# XRP_Controller_Beta.net
KiCad netlist of a schematic drawn in EAGLE
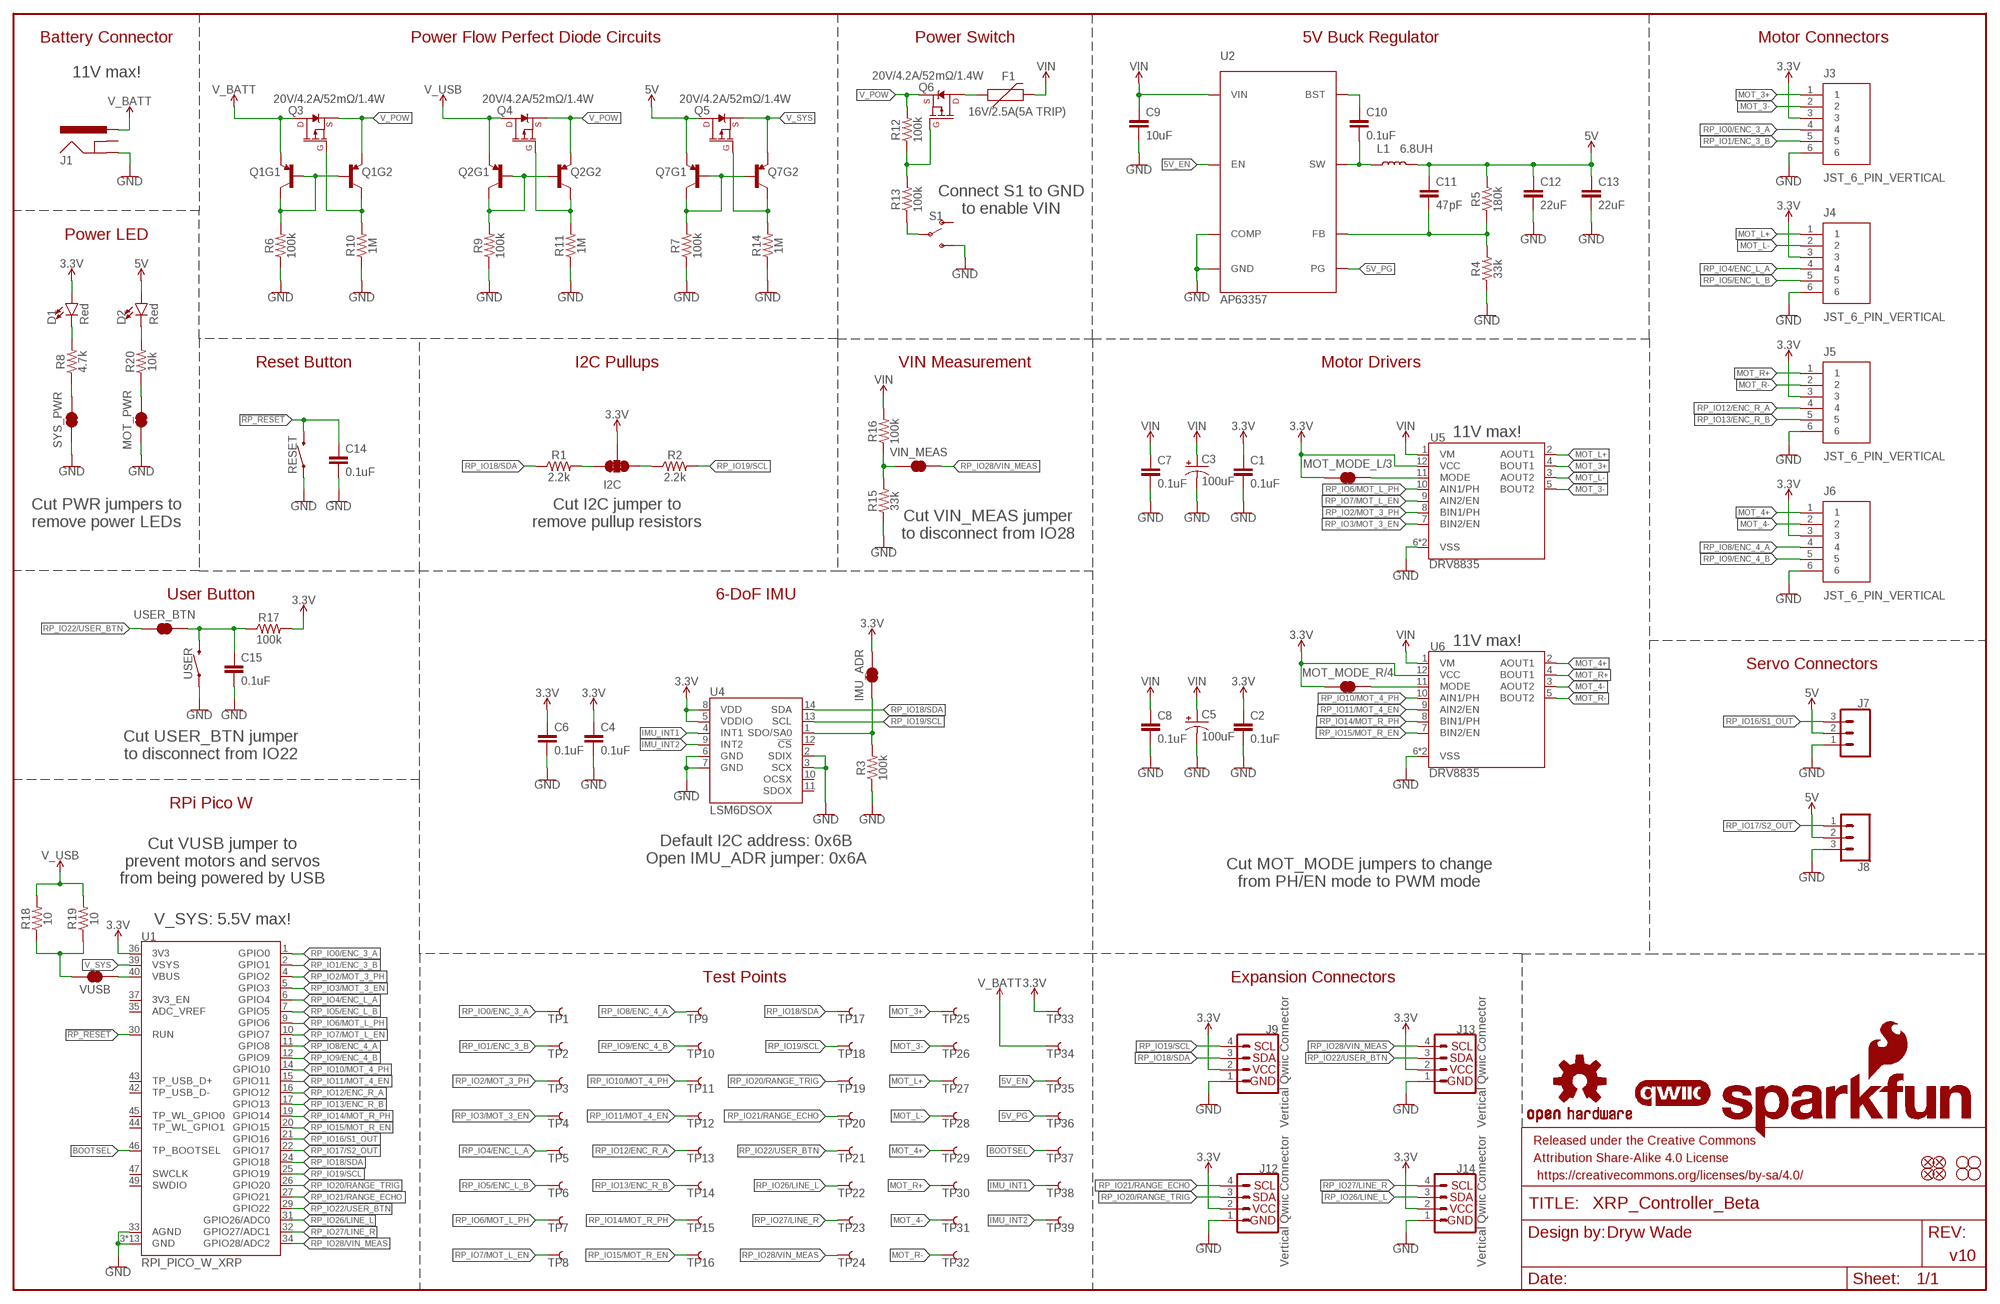
[diagram p0: schematic, sheet 1]

(export (version "E")
  (design (tool "Eeschema 10.0.6"))
  (components
    (comp (ref "C1")
      (value "0.1uF")
      (footprint "eagle-import:0603")
      (libsource (lib "eagle-import") (part "0.1UF-0603-25V-(+80/-20%)"))
    )
    (comp (ref "C2")
      (value "0.1uF")
      (footprint "eagle-import:0603")
      (libsource (lib "eagle-import") (part "0.1UF-0603-25V-(+80/-20%)"))
    )
    (comp (ref "C3")
      (value "100uF")
      (footprint "eagle-import:PANASONIC_D")
      (libsource (lib "eagle-import") (part "100UF-POLAR-25V-20%-SMD(ELEC)"))
    )
    (comp (ref "C4")
      (value "0.1uF")
      (footprint "eagle-import:0603")
      (libsource (lib "eagle-import") (part "0.1UF-0603-25V-(+80/-20%)"))
    )
    (comp (ref "C5")
      (value "100uF")
      (footprint "eagle-import:PANASONIC_D")
      (libsource (lib "eagle-import") (part "100UF-POLAR-25V-20%-SMD(ELEC)"))
    )
    (comp (ref "C6")
      (value "0.1uF")
      (footprint "eagle-import:0603")
      (libsource (lib "eagle-import") (part "0.1UF-0603-25V-(+80/-20%)"))
    )
    (comp (ref "C7")
      (value "0.1uF")
      (footprint "eagle-import:0603")
      (libsource (lib "eagle-import") (part "0.1UF-0603-25V-(+80/-20%)"))
    )
    (comp (ref "C8")
      (value "0.1uF")
      (footprint "eagle-import:0603")
      (libsource (lib "eagle-import") (part "0.1UF-0603-25V-(+80/-20%)"))
    )
    (comp (ref "C9")
      (value "10uF")
      (footprint "eagle-import:0805")
      (libsource (lib "eagle-import") (part "10UF-0805-25V-10%"))
    )
    (comp (ref "C10")
      (value "0.1uF")
      (footprint "eagle-import:0603")
      (libsource (lib "eagle-import") (part "0.1UF-0603-25V-(+80/-20%)"))
    )
    (comp (ref "C11")
      (value "47pF")
      (footprint "eagle-import:0603")
      (libsource (lib "eagle-import") (part "47PF-0603-50V-5%"))
    )
    (comp (ref "C12")
      (value "22uF")
      (footprint "eagle-import:0805")
      (libsource (lib "eagle-import") (part "22UF-0805-16V-20%"))
    )
    (comp (ref "C13")
      (value "22uF")
      (footprint "eagle-import:0805")
      (libsource (lib "eagle-import") (part "22UF-0805-16V-20%"))
    )
    (comp (ref "C14")
      (value "0.1uF")
      (footprint "eagle-import:0603")
      (libsource (lib "eagle-import") (part "0.1UF-0603-25V-(+80/-20%)"))
    )
    (comp (ref "C15")
      (value "0.1uF")
      (footprint "eagle-import:0603")
      (libsource (lib "eagle-import") (part "0.1UF-0603-25V-(+80/-20%)"))
    )
    (comp (ref "D1")
      (value "Red")
      (footprint "eagle-import:LED-0603")
      (libsource (lib "eagle-import") (part "LED-RED_0603-KB"))
    )
    (comp (ref "D2")
      (value "Red")
      (footprint "eagle-import:LED-0603")
      (libsource (lib "eagle-import") (part "LED-RED_0603-KB"))
    )
    (comp (ref "F1")
      (value "16V/2.5A(5A TRIP)")
      (footprint "eagle-import:1812")
      (libsource (lib "eagle-import") (part "PPTC_16V_2.5A"))
    )
    (comp (ref "FD1")
      (value "FIDUCIAL1X2")
      (footprint "eagle-import:FIDUCIAL-1X2")
      (libsource (lib "eagle-import") (part "FIDUCIAL1X2"))
    )
    (comp (ref "FD2")
      (value "FIDUCIAL1X2")
      (footprint "eagle-import:FIDUCIAL-1X2")
      (libsource (lib "eagle-import") (part "FIDUCIAL1X2"))
    )
    (comp (ref "FD3")
      (value "FIDUCIAL1X2")
      (footprint "eagle-import:FIDUCIAL-1X2")
      (libsource (lib "eagle-import") (part "FIDUCIAL1X2"))
    )
    (comp (ref "FD4")
      (value "FIDUCIAL1X2")
      (footprint "eagle-import:FIDUCIAL-1X2")
      (libsource (lib "eagle-import") (part "FIDUCIAL1X2"))
    )
    (comp (ref "FRAME1")
      (value "FRAME-LEDGER")
      (footprint "eagle-import:CREATIVE_COMMONS")
      (libsource (lib "eagle-import") (part "FRAME-LEDGER"))
    )
    (comp (ref "H1")
      (value "STAND-OFF")
      (footprint "eagle-import:STAND-OFF")
      (libsource (lib "eagle-import") (part "STAND-OFF"))
    )
    (comp (ref "H2")
      (value "STAND-OFF")
      (footprint "eagle-import:STAND-OFF")
      (libsource (lib "eagle-import") (part "STAND-OFF"))
    )
    (comp (ref "H3")
      (value "STAND-OFF")
      (footprint "eagle-import:STAND-OFF")
      (libsource (lib "eagle-import") (part "STAND-OFF"))
    )
    (comp (ref "H4")
      (value "STAND-OFF")
      (footprint "eagle-import:STAND-OFF")
      (libsource (lib "eagle-import") (part "STAND-OFF"))
    )
    (comp (ref "I2C")
      (value "JUMPER-SMT_3_2-NC_TRACE_SILK")
      (footprint "eagle-import:SMT-JUMPER_3_2-NC_TRACE_SILK")
      (libsource (lib "eagle-import") (part "JUMPER-SMT_3_2-NC_TRACE_SILK"))
    )
    (comp (ref "IMU_ADR")
      (value "JUMPER-SMT_2_NC_TRACE_SILK")
      (footprint "eagle-import:SMT-JUMPER_2_NC_TRACE_SILK")
      (libsource (lib "eagle-import") (part "JUMPER-SMT_2_NC_TRACE_SILK"))
    )
    (comp (ref "J1")
      (value "POWER_JACKPOWER_JACK_SLOT")
      (footprint "eagle-import:POWER_JACK_PTH_SLOT")
      (libsource (lib "eagle-import") (part "POWER_JACKPOWER_JACK_SLOT"))
    )
    (comp (ref "J3")
      (value "JST_6_PIN_VERTICAL")
      (footprint "eagle-import:JST-6-SMD-VERT-1.0MM")
      (libsource (lib "eagle-import") (part "JST_6_PIN_VERTICAL"))
    )
    (comp (ref "J4")
      (value "JST_6_PIN_VERTICAL")
      (footprint "eagle-import:JST-6-SMD-VERT-1.0MM")
      (libsource (lib "eagle-import") (part "JST_6_PIN_VERTICAL"))
    )
    (comp (ref "J5")
      (value "JST_6_PIN_VERTICAL")
      (footprint "eagle-import:JST-6-SMD-VERT-1.0MM")
      (libsource (lib "eagle-import") (part "JST_6_PIN_VERTICAL"))
    )
    (comp (ref "J6")
      (value "JST_6_PIN_VERTICAL")
      (footprint "eagle-import:JST-6-SMD-VERT-1.0MM")
      (libsource (lib "eagle-import") (part "JST_6_PIN_VERTICAL"))
    )
    (comp (ref "J7")
      (value "CONN_03LOCK_NO_SILK")
      (footprint "eagle-import:1X03_LOCK_NO_SILK")
      (libsource (lib "eagle-import") (part "CONN_03LOCK_NO_SILK"))
    )
    (comp (ref "J8")
      (value "CONN_03LOCK_NO_SILK")
      (footprint "eagle-import:1X03_LOCK_NO_SILK")
      (libsource (lib "eagle-import") (part "CONN_03LOCK_NO_SILK"))
    )
    (comp (ref "J9")
      (value "Vertical Qwiic Connector")
      (footprint "eagle-import:JST04_1MM_VERT")
      (libsource (lib "eagle-import") (part "QWIIC_CONNECTOR"))
    )
    (comp (ref "J12")
      (value "Vertical Qwiic Connector")
      (footprint "eagle-import:JST04_1MM_VERT")
      (libsource (lib "eagle-import") (part "QWIIC_CONNECTOR"))
    )
    (comp (ref "J13")
      (value "Vertical Qwiic Connector")
      (footprint "eagle-import:JST04_1MM_VERT")
      (libsource (lib "eagle-import") (part "QWIIC_CONNECTOR"))
    )
    (comp (ref "J14")
      (value "Vertical Qwiic Connector")
      (footprint "eagle-import:JST04_1MM_VERT")
      (libsource (lib "eagle-import") (part "QWIIC_CONNECTOR"))
    )
    (comp (ref "L1")
      (value "6.8UH")
      (footprint "eagle-import:07A7_6U8H")
      (libsource (lib "eagle-import") (part "6.8UH"))
    )
    (comp (ref "LOGO1")
      (value "OSHW-LOGOS")
      (footprint "eagle-import:OSHW-LOGO-S")
      (libsource (lib "eagle-import") (part "OSHW-LOGOS"))
    )
    (comp (ref "LOGO3")
      (value "SFE_LOGO_NAME_FLAME.3_INCH")
      (footprint "eagle-import:SFE_LOGO_NAME_FLAME_.3")
      (libsource (lib "eagle-import") (part "SFE_LOGO_NAME_FLAME.3_INCH"))
    )
    (comp (ref "MOT_MODE_L/3")
      (value "JUMPER-SMT_2_NC_TRACE_SILK")
      (footprint "eagle-import:SMT-JUMPER_2_NC_TRACE_SILK")
      (libsource (lib "eagle-import") (part "JUMPER-SMT_2_NC_TRACE_SILK"))
    )
    (comp (ref "MOT_MODE_R/4")
      (value "JUMPER-SMT_2_NC_TRACE_SILK")
      (footprint "eagle-import:SMT-JUMPER_2_NC_TRACE_SILK")
      (libsource (lib "eagle-import") (part "JUMPER-SMT_2_NC_TRACE_SILK"))
    )
    (comp (ref "MOT_PWR")
      (value "JUMPER-SMT_2_NC_TRACE_SILK")
      (footprint "eagle-import:SMT-JUMPER_2_NC_TRACE_SILK")
      (libsource (lib "eagle-import") (part "JUMPER-SMT_2_NC_TRACE_SILK"))
    )
    (comp (ref "Q1")
      (value "TRANS_PNP_DUALSOT-363")
      (footprint "eagle-import:SOT363_PHILIPS")
      (libsource (lib "eagle-import") (part "TRANS_PNP_DUALSOT-363"))
    )
    (comp (ref "Q2")
      (value "TRANS_PNP_DUALSOT-363")
      (footprint "eagle-import:SOT363_PHILIPS")
      (libsource (lib "eagle-import") (part "TRANS_PNP_DUALSOT-363"))
    )
    (comp (ref "Q3")
      (value "20V/4.2A/52mΩ/1.4W")
      (footprint "eagle-import:SOT23-3")
      (libsource (lib "eagle-import") (part "MOSFET_PCH-DMG2305UX-7"))
    )
    (comp (ref "Q4")
      (value "20V/4.2A/52mΩ/1.4W")
      (footprint "eagle-import:SOT23-3")
      (libsource (lib "eagle-import") (part "MOSFET_PCH-DMG2305UX-7"))
    )
    (comp (ref "Q5")
      (value "20V/4.2A/52mΩ/1.4W")
      (footprint "eagle-import:SOT23-3")
      (libsource (lib "eagle-import") (part "MOSFET_PCH-DMG2305UX-7"))
    )
    (comp (ref "Q6")
      (value "20V/4.2A/52mΩ/1.4W")
      (footprint "eagle-import:SOT23-3")
      (libsource (lib "eagle-import") (part "MOSFET_PCH-DMG2305UX-7"))
    )
    (comp (ref "Q7")
      (value "TRANS_PNP_DUALSOT-363")
      (footprint "eagle-import:SOT363_PHILIPS")
      (libsource (lib "eagle-import") (part "TRANS_PNP_DUALSOT-363"))
    )
    (comp (ref "R1")
      (value "2.2k")
      (footprint "eagle-import:0603")
      (libsource (lib "eagle-import") (part "2.2KOHM-0603-1/10W-1%"))
    )
    (comp (ref "R2")
      (value "2.2k")
      (footprint "eagle-import:0603")
      (libsource (lib "eagle-import") (part "2.2KOHM-0603-1/10W-1%"))
    )
    (comp (ref "R3")
      (value "100k")
      (footprint "eagle-import:0603")
      (libsource (lib "eagle-import") (part "100KOHM-0603-1/10W-1%"))
    )
    (comp (ref "R4")
      (value "33k")
      (footprint "eagle-import:0603")
      (libsource (lib "eagle-import") (part "33KOHM-0603-1/10W-1%"))
    )
    (comp (ref "R5")
      (value "180k")
      (footprint "eagle-import:0603")
      (libsource (lib "eagle-import") (part "180KOHM-0603-1/10W-1%"))
    )
    (comp (ref "R6")
      (value "100k")
      (footprint "eagle-import:0603")
      (libsource (lib "eagle-import") (part "100KOHM-0603-1/10W-1%"))
    )
    (comp (ref "R7")
      (value "100k")
      (footprint "eagle-import:0603")
      (libsource (lib "eagle-import") (part "100KOHM-0603-1/10W-1%"))
    )
    (comp (ref "R8")
      (value "4.7k")
      (footprint "eagle-import:0603")
      (libsource (lib "eagle-import") (part "4.7KOHM-0603-1/10W-1%"))
    )
    (comp (ref "R9")
      (value "100k")
      (footprint "eagle-import:0603")
      (libsource (lib "eagle-import") (part "100KOHM-0603-1/10W-1%"))
    )
    (comp (ref "R10")
      (value "1M")
      (footprint "eagle-import:0603")
      (libsource (lib "eagle-import") (part "1MOHM-0603-1/4W-5%"))
    )
    (comp (ref "R11")
      (value "1M")
      (footprint "eagle-import:0603")
      (libsource (lib "eagle-import") (part "1MOHM-0603-1/4W-5%"))
    )
    (comp (ref "R12")
      (value "100k")
      (footprint "eagle-import:0603")
      (libsource (lib "eagle-import") (part "100KOHM-0603-1/10W-1%"))
    )
    (comp (ref "R13")
      (value "100k")
      (footprint "eagle-import:0603")
      (libsource (lib "eagle-import") (part "100KOHM-0603-1/10W-1%"))
    )
    (comp (ref "R14")
      (value "1M")
      (footprint "eagle-import:0603")
      (libsource (lib "eagle-import") (part "1MOHM-0603-1/4W-5%"))
    )
    (comp (ref "R15")
      (value "33k")
      (footprint "eagle-import:0603")
      (libsource (lib "eagle-import") (part "33KOHM-0603-1/10W-1%"))
    )
    (comp (ref "R16")
      (value "100k")
      (footprint "eagle-import:0603")
      (libsource (lib "eagle-import") (part "100KOHM-0603-1/10W-1%"))
    )
    (comp (ref "R17")
      (value "100k")
      (footprint "eagle-import:0603")
      (libsource (lib "eagle-import") (part "100KOHM-0603-1/10W-1%"))
    )
    (comp (ref "R18")
      (value "10")
      (footprint "eagle-import:1206")
      (libsource (lib "eagle-import") (part "10OHM-1206-1/4W-1%"))
    )
    (comp (ref "R19")
      (value "10")
      (footprint "eagle-import:1206")
      (libsource (lib "eagle-import") (part "10OHM-1206-1/4W-1%"))
    )
    (comp (ref "R20")
      (value "10k")
      (footprint "eagle-import:0603")
      (libsource (lib "eagle-import") (part "10KOHM-0603-1/10W-1%"))
    )
    (comp (ref "RESET")
      (value "MOMENTARY-SWITCH-SPST-SMD-4.6X2.8MM")
      (footprint "eagle-import:TACTILE_SWITCH_SMD_4.6X2.8MM")
      (libsource (lib "eagle-import") (part "MOMENTARY-SWITCH-SPST-SMD-4.6X2.8MM"))
    )
    (comp (ref "S1")
      (value "SWITCH-SPDT-SMD-RIGHT-ANGLE")
      (footprint "eagle-import:SWITCH_SPST_SMD_A")
      (libsource (lib "eagle-import") (part "SWITCH-SPDT-SMD-RIGHT-ANGLE"))
    )
    (comp (ref "SYS_PWR")
      (value "JUMPER-SMT_2_NC_TRACE_SILK")
      (footprint "eagle-import:SMT-JUMPER_2_NC_TRACE_SILK")
      (libsource (lib "eagle-import") (part "JUMPER-SMT_2_NC_TRACE_SILK"))
    )
    (comp (ref "TP1")
      (value "TEST-POINT3X5")
      (footprint "eagle-import:PAD.03X.05")
      (libsource (lib "eagle-import") (part "TEST-POINT3X5"))
    )
    (comp (ref "TP2")
      (value "TEST-POINT3X5")
      (footprint "eagle-import:PAD.03X.05")
      (libsource (lib "eagle-import") (part "TEST-POINT3X5"))
    )
    (comp (ref "TP3")
      (value "TEST-POINT3X5")
      (footprint "eagle-import:PAD.03X.05")
      (libsource (lib "eagle-import") (part "TEST-POINT3X5"))
    )
    (comp (ref "TP4")
      (value "TEST-POINT3X5")
      (footprint "eagle-import:PAD.03X.05")
      (libsource (lib "eagle-import") (part "TEST-POINT3X5"))
    )
    (comp (ref "TP5")
      (value "TEST-POINT3X5")
      (footprint "eagle-import:PAD.03X.05")
      (libsource (lib "eagle-import") (part "TEST-POINT3X5"))
    )
    (comp (ref "TP6")
      (value "TEST-POINT3X5")
      (footprint "eagle-import:PAD.03X.05")
      (libsource (lib "eagle-import") (part "TEST-POINT3X5"))
    )
    (comp (ref "TP7")
      (value "TEST-POINT3X5")
      (footprint "eagle-import:PAD.03X.05")
      (libsource (lib "eagle-import") (part "TEST-POINT3X5"))
    )
    (comp (ref "TP8")
      (value "TEST-POINT3X5")
      (footprint "eagle-import:PAD.03X.05")
      (libsource (lib "eagle-import") (part "TEST-POINT3X5"))
    )
    (comp (ref "TP9")
      (value "TEST-POINT3X5")
      (footprint "eagle-import:PAD.03X.05")
      (libsource (lib "eagle-import") (part "TEST-POINT3X5"))
    )
    (comp (ref "TP10")
      (value "TEST-POINT3X5")
      (footprint "eagle-import:PAD.03X.05")
      (libsource (lib "eagle-import") (part "TEST-POINT3X5"))
    )
    (comp (ref "TP11")
      (value "TEST-POINT3X5")
      (footprint "eagle-import:PAD.03X.05")
      (libsource (lib "eagle-import") (part "TEST-POINT3X5"))
    )
    (comp (ref "TP12")
      (value "TEST-POINT3X5")
      (footprint "eagle-import:PAD.03X.05")
      (libsource (lib "eagle-import") (part "TEST-POINT3X5"))
    )
    (comp (ref "TP13")
      (value "TEST-POINT3X5")
      (footprint "eagle-import:PAD.03X.05")
      (libsource (lib "eagle-import") (part "TEST-POINT3X5"))
    )
    (comp (ref "TP14")
      (value "TEST-POINT3X5")
      (footprint "eagle-import:PAD.03X.05")
      (libsource (lib "eagle-import") (part "TEST-POINT3X5"))
    )
    (comp (ref "TP15")
      (value "TEST-POINT3X5")
      (footprint "eagle-import:PAD.03X.05")
      (libsource (lib "eagle-import") (part "TEST-POINT3X5"))
    )
    (comp (ref "TP16")
      (value "TEST-POINT3X5")
      (footprint "eagle-import:PAD.03X.05")
      (libsource (lib "eagle-import") (part "TEST-POINT3X5"))
    )
    (comp (ref "TP17")
      (value "TEST-POINT3X5")
      (footprint "eagle-import:PAD.03X.05")
      (libsource (lib "eagle-import") (part "TEST-POINT3X5"))
    )
    (comp (ref "TP18")
      (value "TEST-POINT3X5")
      (footprint "eagle-import:PAD.03X.05")
      (libsource (lib "eagle-import") (part "TEST-POINT3X5"))
    )
    (comp (ref "TP19")
      (value "TEST-POINT3X5")
      (footprint "eagle-import:PAD.03X.05")
      (libsource (lib "eagle-import") (part "TEST-POINT3X5"))
    )
    (comp (ref "TP20")
      (value "TEST-POINT3X5")
      (footprint "eagle-import:PAD.03X.05")
      (libsource (lib "eagle-import") (part "TEST-POINT3X5"))
    )
    (comp (ref "TP21")
      (value "TEST-POINT3X5")
      (footprint "eagle-import:PAD.03X.05")
      (libsource (lib "eagle-import") (part "TEST-POINT3X5"))
    )
    (comp (ref "TP22")
      (value "TEST-POINT3X5")
      (footprint "eagle-import:PAD.03X.05")
      (libsource (lib "eagle-import") (part "TEST-POINT3X5"))
    )
    (comp (ref "TP23")
      (value "TEST-POINT3X5")
      (footprint "eagle-import:PAD.03X.05")
      (libsource (lib "eagle-import") (part "TEST-POINT3X5"))
    )
    (comp (ref "TP24")
      (value "TEST-POINT3X5")
      (footprint "eagle-import:PAD.03X.05")
      (libsource (lib "eagle-import") (part "TEST-POINT3X5"))
    )
    (comp (ref "TP25")
      (value "TEST-POINT3X5")
      (footprint "eagle-import:PAD.03X.05")
      (libsource (lib "eagle-import") (part "TEST-POINT3X5"))
    )
    (comp (ref "TP26")
      (value "TEST-POINT3X5")
      (footprint "eagle-import:PAD.03X.05")
      (libsource (lib "eagle-import") (part "TEST-POINT3X5"))
    )
    (comp (ref "TP27")
      (value "TEST-POINT3X5")
      (footprint "eagle-import:PAD.03X.05")
      (libsource (lib "eagle-import") (part "TEST-POINT3X5"))
    )
    (comp (ref "TP28")
      (value "TEST-POINT3X5")
      (footprint "eagle-import:PAD.03X.05")
      (libsource (lib "eagle-import") (part "TEST-POINT3X5"))
    )
    (comp (ref "TP29")
      (value "TEST-POINT3X5")
      (footprint "eagle-import:PAD.03X.05")
      (libsource (lib "eagle-import") (part "TEST-POINT3X5"))
    )
    (comp (ref "TP30")
      (value "TEST-POINT3X5")
      (footprint "eagle-import:PAD.03X.05")
      (libsource (lib "eagle-import") (part "TEST-POINT3X5"))
    )
    (comp (ref "TP31")
      (value "TEST-POINT3X5")
      (footprint "eagle-import:PAD.03X.05")
      (libsource (lib "eagle-import") (part "TEST-POINT3X5"))
    )
    (comp (ref "TP32")
      (value "TEST-POINT3X5")
      (footprint "eagle-import:PAD.03X.05")
      (libsource (lib "eagle-import") (part "TEST-POINT3X5"))
    )
    (comp (ref "TP33")
      (value "TEST-POINT3X5")
      (footprint "eagle-import:PAD.03X.05")
      (libsource (lib "eagle-import") (part "TEST-POINT3X5"))
    )
    (comp (ref "TP34")
      (value "TEST-POINT3X5")
      (footprint "eagle-import:PAD.03X.05")
      (libsource (lib "eagle-import") (part "TEST-POINT3X5"))
    )
    (comp (ref "TP35")
      (value "TEST-POINT3X5")
      (footprint "eagle-import:PAD.03X.05")
      (libsource (lib "eagle-import") (part "TEST-POINT3X5"))
    )
    (comp (ref "TP36")
      (value "TEST-POINT3X5")
      (footprint "eagle-import:PAD.03X.05")
      (libsource (lib "eagle-import") (part "TEST-POINT3X5"))
    )
    (comp (ref "TP37")
      (value "TEST-POINT3X5")
      (footprint "eagle-import:PAD.03X.05")
      (libsource (lib "eagle-import") (part "TEST-POINT3X5"))
    )
    (comp (ref "TP38")
      (value "TEST-POINT3X5")
      (footprint "eagle-import:PAD.03X.05")
      (libsource (lib "eagle-import") (part "TEST-POINT3X5"))
    )
    (comp (ref "TP39")
      (value "TEST-POINT3X5")
      (footprint "eagle-import:PAD.03X.05")
      (libsource (lib "eagle-import") (part "TEST-POINT3X5"))
    )
    (comp (ref "U$98")
      (value "QWIIC_LOGO_5MM_INVERTED")
      (footprint "eagle-import:QWIIC_5MM_INVERTED")
      (libsource (lib "eagle-import") (part "QWIIC_LOGO_5MM_INVERTED"))
    )
    (comp (ref "U1")
      (value "RPI_PICO_W_XRP")
      (footprint "eagle-import:RPI_PICO_W")
      (libsource (lib "eagle-import") (part "RPI_PICO_W_XRP"))
    )
    (comp (ref "U2")
      (value "AP63357")
      (footprint "eagle-import:V-DFN3020-13")
      (libsource (lib "eagle-import") (part "AP63357"))
    )
    (comp (ref "U4")
      (value "LSM6DSOX")
      (footprint "eagle-import:LGA14L")
      (libsource (lib "eagle-import") (part "LSM6DSOX"))
    )
    (comp (ref "U5")
      (value "DRV8835")
      (footprint "eagle-import:WSON-12")
      (libsource (lib "eagle-import") (part "DRV883X"))
    )
    (comp (ref "U6")
      (value "DRV8835")
      (footprint "eagle-import:WSON-12")
      (libsource (lib "eagle-import") (part "DRV883X"))
    )
    (comp (ref "USER")
      (value "MOMENTARY-SWITCH-SPST-SMD-4.6X2.8MM")
      (footprint "eagle-import:TACTILE_SWITCH_SMD_4.6X2.8MM")
      (libsource (lib "eagle-import") (part "MOMENTARY-SWITCH-SPST-SMD-4.6X2.8MM"))
    )
    (comp (ref "USER_BTN")
      (value "JUMPER-SMT_2_NC_TRACE_SILK")
      (footprint "eagle-import:SMT-JUMPER_2_NC_TRACE_SILK")
      (libsource (lib "eagle-import") (part "JUMPER-SMT_2_NC_TRACE_SILK"))
    )
    (comp (ref "VIN_MEAS")
      (value "JUMPER-SMT_2_NC_TRACE_SILK")
      (footprint "eagle-import:SMT-JUMPER_2_NC_TRACE_SILK")
      (libsource (lib "eagle-import") (part "JUMPER-SMT_2_NC_TRACE_SILK"))
    )
    (comp (ref "VUSB")
      (value "JUMPER-SMT_2_NC_TRACE_SILK")
      (footprint "eagle-import:SMT-JUMPER_2_NC_TRACE_SILK")
      (libsource (lib "eagle-import") (part "JUMPER-SMT_2_NC_TRACE_SILK"))
    )
  )
  (nets
    (net (code "1") (name "/~{RP_RESET}") (class "Default")
      (node (ref "C14") (pin "1") (pinfunction "1_1") (pintype "passive"))
      (node (ref "RESET") (pin "3") (pinfunction "2_3") (pintype "passive"))
      (node (ref "RESET") (pin "4") (pinfunction "2_4") (pintype "passive"))
      (node (ref "U1") (pin "30") (pinfunction "RUN_30") (pintype "bidirectional"))
    )
    (net (code "2") (name "3.3V") (class "Default")
      (node (ref "C1") (pin "1") (pinfunction "1_1") (pintype "passive"))
      (node (ref "C2") (pin "1") (pinfunction "1_1") (pintype "passive"))
      (node (ref "C4") (pin "1") (pinfunction "1_1") (pintype "passive"))
      (node (ref "C6") (pin "1") (pinfunction "1_1") (pintype "passive"))
      (node (ref "D1") (pin "A") (pinfunction "A_A") (pintype "passive"))
      (node (ref "I2C") (pin "2") (pinfunction "2_2") (pintype "passive"))
      (node (ref "IMU_ADR") (pin "2") (pinfunction "2_2") (pintype "passive"))
      (node (ref "J12") (pin "2") (pinfunction "2_2") (pintype "power_in"))
      (node (ref "J13") (pin "2") (pinfunction "2_2") (pintype "power_in"))
      (node (ref "J14") (pin "2") (pinfunction "2_2") (pintype "power_in"))
      (node (ref "J3") (pin "3") (pinfunction "3_3") (pintype "bidirectional"))
      (node (ref "J4") (pin "3") (pinfunction "3_3") (pintype "bidirectional"))
      (node (ref "J5") (pin "3") (pinfunction "3_3") (pintype "bidirectional"))
      (node (ref "J6") (pin "3") (pinfunction "3_3") (pintype "bidirectional"))
      (node (ref "J9") (pin "2") (pinfunction "2_2") (pintype "power_in"))
      (node (ref "MOT_MODE_L/3") (pin "2") (pinfunction "2_2") (pintype "passive"))
      (node (ref "MOT_MODE_R/4") (pin "2") (pinfunction "2_2") (pintype "passive"))
      (node (ref "R17") (pin "2") (pinfunction "2_2") (pintype "passive"))
      (node (ref "TP33") (pin "1") (pinfunction "1_1") (pintype "bidirectional"))
      (node (ref "U1") (pin "36") (pinfunction "3V3_36") (pintype "bidirectional"))
      (node (ref "U4") (pin "5") (pinfunction "VDDIO_5") (pintype "bidirectional"))
      (node (ref "U4") (pin "8") (pinfunction "VDD_8") (pintype "bidirectional"))
      (node (ref "U5") (pin "12") (pinfunction "VCC_12") (pintype "bidirectional"))
      (node (ref "U6") (pin "12") (pinfunction "VCC_12") (pintype "bidirectional"))
    )
    (net (code "3") (name "5V") (class "Default")
      (node (ref "C11") (pin "1") (pinfunction "1_1") (pintype "passive"))
      (node (ref "C12") (pin "1") (pinfunction "1_1") (pintype "passive"))
      (node (ref "C13") (pin "1") (pinfunction "1_1") (pintype "passive"))
      (node (ref "D2") (pin "A") (pinfunction "A_A") (pintype "passive"))
      (node (ref "J7") (pin "2") (pinfunction "2_2") (pintype "passive"))
      (node (ref "J8") (pin "2") (pinfunction "2_2") (pintype "passive"))
      (node (ref "L1") (pin "P$2") (pinfunction "2_P$2") (pintype "passive"))
      (node (ref "Q5") (pin "3") (pinfunction "D_3") (pintype "bidirectional"))
      (node (ref "Q7") (pin "1") (pinfunction "E_1") (pintype "passive"))
      (node (ref "R5") (pin "2") (pinfunction "2_2") (pintype "passive"))
    )
    (net (code "4") (name "5V_EN") (class "Default")
      (node (ref "TP35") (pin "1") (pinfunction "1_1") (pintype "bidirectional"))
      (node (ref "U2") (pin "P$2") (pinfunction "EN_P$2") (pintype "bidirectional"))
    )
    (net (code "5") (name "5V_PG") (class "Default")
      (node (ref "TP36") (pin "1") (pinfunction "1_1") (pintype "bidirectional"))
      (node (ref "U2") (pin "P$5") (pinfunction "PG_P$5") (pintype "output"))
    )
    (net (code "6") (name "BOOTSEL") (class "Default")
      (node (ref "TP37") (pin "1") (pinfunction "1_1") (pintype "bidirectional"))
      (node (ref "U1") (pin "46") (pinfunction "TP_BOOTSEL_46") (pintype "bidirectional"))
    )
    (net (code "7") (name "GND") (class "Default")
      (node (ref "C1") (pin "2") (pinfunction "2_2") (pintype "passive"))
      (node (ref "C12") (pin "2") (pinfunction "2_2") (pintype "passive"))
      (node (ref "C13") (pin "2") (pinfunction "2_2") (pintype "passive"))
      (node (ref "C14") (pin "2") (pinfunction "2_2") (pintype "passive"))
      (node (ref "C15") (pin "2") (pinfunction "2_2") (pintype "passive"))
      (node (ref "C2") (pin "2") (pinfunction "2_2") (pintype "passive"))
      (node (ref "C3") (pin "-") (pinfunction "-_-") (pintype "passive"))
      (node (ref "C4") (pin "2") (pinfunction "2_2") (pintype "passive"))
      (node (ref "C5") (pin "-") (pinfunction "-_-") (pintype "passive"))
      (node (ref "C6") (pin "2") (pinfunction "2_2") (pintype "passive"))
      (node (ref "C7") (pin "2") (pinfunction "2_2") (pintype "passive"))
      (node (ref "C8") (pin "2") (pinfunction "2_2") (pintype "passive"))
      (node (ref "C9") (pin "2") (pinfunction "2_2") (pintype "passive"))
      (node (ref "J1") (pin "GND") (pinfunction "GND_GND") (pintype "bidirectional"))
      (node (ref "J12") (pin "1") (pinfunction "1_1") (pintype "power_in"))
      (node (ref "J13") (pin "1") (pinfunction "1_1") (pintype "power_in"))
      (node (ref "J14") (pin "1") (pinfunction "1_1") (pintype "power_in"))
      (node (ref "J3") (pin "6") (pinfunction "6_6") (pintype "bidirectional"))
      (node (ref "J4") (pin "6") (pinfunction "6_6") (pintype "bidirectional"))
      (node (ref "J5") (pin "6") (pinfunction "6_6") (pintype "bidirectional"))
      (node (ref "J6") (pin "6") (pinfunction "6_6") (pintype "bidirectional"))
      (node (ref "J7") (pin "1") (pinfunction "1_1") (pintype "passive"))
      (node (ref "J8") (pin "3") (pinfunction "3_3") (pintype "passive"))
      (node (ref "J9") (pin "1") (pinfunction "1_1") (pintype "power_in"))
      (node (ref "MOT_PWR") (pin "1") (pinfunction "1_1") (pintype "passive"))
      (node (ref "R10") (pin "1") (pinfunction "1_1") (pintype "passive"))
      (node (ref "R11") (pin "1") (pinfunction "1_1") (pintype "passive"))
      (node (ref "R14") (pin "1") (pinfunction "1_1") (pintype "passive"))
      (node (ref "R15") (pin "1") (pinfunction "1_1") (pintype "passive"))
      (node (ref "R3") (pin "1") (pinfunction "1_1") (pintype "passive"))
      (node (ref "R4") (pin "1") (pinfunction "1_1") (pintype "passive"))
      (node (ref "R6") (pin "1") (pinfunction "1_1") (pintype "passive"))
      (node (ref "R7") (pin "1") (pinfunction "1_1") (pintype "passive"))
      (node (ref "R9") (pin "1") (pinfunction "1_1") (pintype "passive"))
      (node (ref "RESET") (pin "1") (pinfunction "1_1") (pintype "passive"))
      (node (ref "RESET") (pin "2") (pinfunction "1_2") (pintype "passive"))
      (node (ref "S1") (pin "3") (pinfunction "S_3") (pintype "passive"))
      (node (ref "SYS_PWR") (pin "1") (pinfunction "1_1") (pintype "passive"))
      (node (ref "U1") (pin "13") (pinfunction "GND_13") (pintype "bidirectional"))
      (node (ref "U1") (pin "18") (pinfunction "GND_18") (pintype "bidirectional"))
      (node (ref "U1") (pin "23") (pinfunction "GND_23") (pintype "bidirectional"))
      (node (ref "U1") (pin "28") (pinfunction "GND_28") (pintype "bidirectional"))
      (node (ref "U1") (pin "3") (pinfunction "GND_3") (pintype "bidirectional"))
      (node (ref "U1") (pin "33") (pinfunction "AGND_33") (pintype "bidirectional"))
      (node (ref "U1") (pin "38") (pinfunction "GND_38") (pintype "bidirectional"))
      (node (ref "U1") (pin "41") (pinfunction "GND_41") (pintype "bidirectional"))
      (node (ref "U1") (pin "48") (pinfunction "GND_48") (pintype "bidirectional"))
      (node (ref "U1") (pin "8") (pinfunction "GND_8") (pintype "bidirectional"))
      (node (ref "U1") (pin "A") (pinfunction "GND_A") (pintype "bidirectional"))
      (node (ref "U1") (pin "B") (pinfunction "GND_B") (pintype "bidirectional"))
      (node (ref "U1") (pin "C") (pinfunction "GND_C") (pintype "bidirectional"))
      (node (ref "U1") (pin "D") (pinfunction "GND_D") (pintype "bidirectional"))
      (node (ref "U2") (pin "P$4") (pinfunction "COMP_P$4") (pintype "bidirectional"))
      (node (ref "U2") (pin "P$8") (pinfunction "GND_P$8") (pintype "power_in"))
      (node (ref "U4") (pin "2") (pinfunction "SDIX_2") (pintype "bidirectional"))
      (node (ref "U4") (pin "3") (pinfunction "SCX_3") (pintype "bidirectional"))
      (node (ref "U4") (pin "6") (pinfunction "GND_6") (pintype "bidirectional"))
      (node (ref "U4") (pin "7") (pinfunction "GND_7") (pintype "bidirectional"))
      (node (ref "U5") (pin "6") (pinfunction "VSS_6") (pintype "bidirectional"))
      (node (ref "U5") (pin "PAD") (pinfunction "VSS_PAD") (pintype "bidirectional"))
      (node (ref "U6") (pin "6") (pinfunction "VSS_6") (pintype "bidirectional"))
      (node (ref "U6") (pin "PAD") (pinfunction "VSS_PAD") (pintype "bidirectional"))
      (node (ref "USER") (pin "1") (pinfunction "1_1") (pintype "passive"))
      (node (ref "USER") (pin "2") (pinfunction "1_2") (pintype "passive"))
    )
    (net (code "8") (name "IMU_INT1") (class "Default")
      (node (ref "TP38") (pin "1") (pinfunction "1_1") (pintype "bidirectional"))
      (node (ref "U4") (pin "4") (pinfunction "INT1_4") (pintype "bidirectional"))
    )
    (net (code "9") (name "IMU_INT2") (class "Default")
      (node (ref "TP39") (pin "1") (pinfunction "1_1") (pintype "bidirectional"))
      (node (ref "U4") (pin "9") (pinfunction "INT2_9") (pintype "bidirectional"))
    )
    (net (code "10") (name "MOT_3+") (class "Default")
      (node (ref "J3") (pin "1") (pinfunction "1_1") (pintype "bidirectional"))
      (node (ref "TP25") (pin "1") (pinfunction "1_1") (pintype "bidirectional"))
      (node (ref "U5") (pin "4") (pinfunction "BOUT1_4") (pintype "bidirectional"))
    )
    (net (code "11") (name "MOT_3-") (class "Default")
      (node (ref "J3") (pin "2") (pinfunction "2_2") (pintype "bidirectional"))
      (node (ref "TP26") (pin "1") (pinfunction "1_1") (pintype "bidirectional"))
      (node (ref "U5") (pin "5") (pinfunction "BOUT2_5") (pintype "bidirectional"))
    )
    (net (code "12") (name "MOT_4+") (class "Default")
      (node (ref "J6") (pin "1") (pinfunction "1_1") (pintype "bidirectional"))
      (node (ref "TP29") (pin "1") (pinfunction "1_1") (pintype "bidirectional"))
      (node (ref "U6") (pin "2") (pinfunction "AOUT1_2") (pintype "bidirectional"))
    )
    (net (code "13") (name "MOT_4-") (class "Default")
      (node (ref "J6") (pin "2") (pinfunction "2_2") (pintype "bidirectional"))
      (node (ref "TP31") (pin "1") (pinfunction "1_1") (pintype "bidirectional"))
      (node (ref "U6") (pin "3") (pinfunction "AOUT2_3") (pintype "bidirectional"))
    )
    (net (code "14") (name "MOT_L+") (class "Default")
      (node (ref "J4") (pin "1") (pinfunction "1_1") (pintype "bidirectional"))
      (node (ref "TP27") (pin "1") (pinfunction "1_1") (pintype "bidirectional"))
      (node (ref "U5") (pin "2") (pinfunction "AOUT1_2") (pintype "bidirectional"))
    )
    (net (code "15") (name "MOT_L-") (class "Default")
      (node (ref "J4") (pin "2") (pinfunction "2_2") (pintype "bidirectional"))
      (node (ref "TP28") (pin "1") (pinfunction "1_1") (pintype "bidirectional"))
      (node (ref "U5") (pin "3") (pinfunction "AOUT2_3") (pintype "bidirectional"))
    )
    (net (code "16") (name "MOT_R+") (class "Default")
      (node (ref "J5") (pin "1") (pinfunction "1_1") (pintype "bidirectional"))
      (node (ref "TP30") (pin "1") (pinfunction "1_1") (pintype "bidirectional"))
      (node (ref "U6") (pin "4") (pinfunction "BOUT1_4") (pintype "bidirectional"))
    )
    (net (code "17") (name "MOT_R-") (class "Default")
      (node (ref "J5") (pin "2") (pinfunction "2_2") (pintype "bidirectional"))
      (node (ref "TP32") (pin "1") (pinfunction "1_1") (pintype "bidirectional"))
      (node (ref "U6") (pin "5") (pinfunction "BOUT2_5") (pintype "bidirectional"))
    )
    (net (code "18") (name "Net-(C15-Pad1)") (class "Default")
      (node (ref "C15") (pin "1") (pinfunction "1_1") (pintype "passive"))
      (node (ref "R17") (pin "1") (pinfunction "1_1") (pintype "passive"))
      (node (ref "USER") (pin "3") (pinfunction "2_3") (pintype "passive"))
      (node (ref "USER") (pin "4") (pinfunction "2_4") (pintype "passive"))
      (node (ref "USER_BTN") (pin "1") (pinfunction "1_1") (pintype "passive"))
    )
    (net (code "19") (name "Net-(D1-PadC)") (class "Default")
      (node (ref "D1") (pin "C") (pinfunction "C_C") (pintype "passive"))
      (node (ref "R8") (pin "2") (pinfunction "2_2") (pintype "passive"))
    )
    (net (code "20") (name "Net-(D2-PadC)") (class "Default")
      (node (ref "D2") (pin "C") (pinfunction "C_C") (pintype "passive"))
      (node (ref "R20") (pin "2") (pinfunction "2_2") (pintype "passive"))
    )
    (net (code "21") (name "Net-(I2C-Pad1)") (class "Default")
      (node (ref "I2C") (pin "1") (pinfunction "1_1") (pintype "passive"))
      (node (ref "R2") (pin "1") (pinfunction "1_1") (pintype "passive"))
    )
    (net (code "22") (name "Net-(I2C-Pad3)") (class "Default")
      (node (ref "I2C") (pin "3") (pinfunction "3_3") (pintype "passive"))
      (node (ref "R1") (pin "2") (pinfunction "2_2") (pintype "passive"))
    )
    (net (code "23") (name "Net-(L1-1)") (class "Default")
      (node (ref "C10") (pin "2") (pinfunction "2_2") (pintype "passive"))
      (node (ref "L1") (pin "P$1") (pinfunction "1_P$1") (pintype "passive"))
      (node (ref "U2") (pin "P$7") (pinfunction "SW_P$7") (pintype "power_in"))
      (node (ref "U2") (pin "P$9") (pinfunction "SW_P$9") (pintype "power_in"))
    )
    (net (code "24") (name "Net-(MOT_PWR-Pad2)") (class "Default")
      (node (ref "MOT_PWR") (pin "2") (pinfunction "2_2") (pintype "passive"))
      (node (ref "R20") (pin "1") (pinfunction "1_1") (pintype "passive"))
    )
    (net (code "25") (name "Net-(Q1A-B)") (class "Default")
      (node (ref "Q1") (pin "2") (pinfunction "B_2") (pintype "passive"))
      (node (ref "Q1") (pin "5") (pinfunction "B_5") (pintype "passive"))
      (node (ref "Q1") (pin "6") (pinfunction "C_6") (pintype "passive"))
      (node (ref "R6") (pin "2") (pinfunction "2_2") (pintype "passive"))
    )
    (net (code "26") (name "Net-(Q1B-C)") (class "Default")
      (node (ref "Q1") (pin "3") (pinfunction "C_3") (pintype "passive"))
      (node (ref "Q3") (pin "1") (pinfunction "G_1") (pintype "bidirectional"))
      (node (ref "R10") (pin "2") (pinfunction "2_2") (pintype "passive"))
    )
    (net (code "27") (name "Net-(Q2A-B)") (class "Default")
      (node (ref "Q2") (pin "2") (pinfunction "B_2") (pintype "passive"))
      (node (ref "Q2") (pin "5") (pinfunction "B_5") (pintype "passive"))
      (node (ref "Q2") (pin "6") (pinfunction "C_6") (pintype "passive"))
      (node (ref "R9") (pin "2") (pinfunction "2_2") (pintype "passive"))
    )
    (net (code "28") (name "Net-(Q2B-C)") (class "Default")
      (node (ref "Q2") (pin "3") (pinfunction "C_3") (pintype "passive"))
      (node (ref "Q4") (pin "1") (pinfunction "G_1") (pintype "bidirectional"))
      (node (ref "R11") (pin "2") (pinfunction "2_2") (pintype "passive"))
    )
    (net (code "29") (name "Net-(Q5-G)") (class "Default")
      (node (ref "Q5") (pin "1") (pinfunction "G_1") (pintype "bidirectional"))
      (node (ref "Q7") (pin "3") (pinfunction "C_3") (pintype "passive"))
      (node (ref "R14") (pin "2") (pinfunction "2_2") (pintype "passive"))
    )
    (net (code "30") (name "Net-(Q6-D)") (class "Default")
      (node (ref "F1") (pin "1") (pinfunction "1_1") (pintype "bidirectional"))
      (node (ref "Q6") (pin "3") (pinfunction "D_3") (pintype "bidirectional"))
    )
    (net (code "31") (name "Net-(Q6-G)") (class "Default")
      (node (ref "Q6") (pin "1") (pinfunction "G_1") (pintype "bidirectional"))
      (node (ref "R12") (pin "1") (pinfunction "1_1") (pintype "passive"))
      (node (ref "R13") (pin "2") (pinfunction "2_2") (pintype "passive"))
    )
    (net (code "32") (name "Net-(Q7A-B)") (class "Default")
      (node (ref "Q7") (pin "2") (pinfunction "B_2") (pintype "passive"))
      (node (ref "Q7") (pin "5") (pinfunction "B_5") (pintype "passive"))
      (node (ref "Q7") (pin "6") (pinfunction "C_6") (pintype "passive"))
      (node (ref "R7") (pin "2") (pinfunction "2_2") (pintype "passive"))
    )
    (net (code "33") (name "Net-(R8-Pad1)") (class "Default")
      (node (ref "R8") (pin "1") (pinfunction "1_1") (pintype "passive"))
      (node (ref "SYS_PWR") (pin "2") (pinfunction "2_2") (pintype "passive"))
    )
    (net (code "34") (name "Net-(R15-Pad2)") (class "Default")
      (node (ref "R15") (pin "2") (pinfunction "2_2") (pintype "passive"))
      (node (ref "R16") (pin "1") (pinfunction "1_1") (pintype "passive"))
      (node (ref "VIN_MEAS") (pin "2") (pinfunction "2_2") (pintype "passive"))
    )
    (net (code "35") (name "Net-(R18-Pad1)") (class "Default")
      (node (ref "R18") (pin "1") (pinfunction "1_1") (pintype "passive"))
      (node (ref "R19") (pin "1") (pinfunction "1_1") (pintype "passive"))
      (node (ref "VUSB") (pin "1") (pinfunction "1_1") (pintype "passive"))
    )
    (net (code "36") (name "Net-(S1-P)") (class "Default")
      (node (ref "R13") (pin "1") (pinfunction "1_1") (pintype "passive"))
      (node (ref "S1") (pin "2") (pinfunction "P_2") (pintype "passive"))
    )
    (net (code "37") (name "Net-(U1-VBUS)") (class "Default")
      (node (ref "U1") (pin "40") (pinfunction "VBUS_40") (pintype "bidirectional"))
      (node (ref "VUSB") (pin "2") (pinfunction "2_2") (pintype "passive"))
    )
    (net (code "38") (name "Net-(U2-BST)") (class "Default")
      (node (ref "C10") (pin "1") (pinfunction "1_1") (pintype "passive"))
      (node (ref "U2") (pin "P$6") (pinfunction "BST_P$6") (pintype "bidirectional"))
    )
    (net (code "39") (name "Net-(U2-FB)") (class "Default")
      (node (ref "C11") (pin "2") (pinfunction "2_2") (pintype "passive"))
      (node (ref "R4") (pin "2") (pinfunction "2_2") (pintype "passive"))
      (node (ref "R5") (pin "1") (pinfunction "1_1") (pintype "passive"))
      (node (ref "U2") (pin "P$3") (pinfunction "FB_P$3") (pintype "input"))
    )
    (net (code "40") (name "Net-(U4-SDO{slash}SA0)") (class "Default")
      (node (ref "IMU_ADR") (pin "1") (pinfunction "1_1") (pintype "passive"))
      (node (ref "R3") (pin "2") (pinfunction "2_2") (pintype "passive"))
      (node (ref "U4") (pin "1") (pinfunction "SDO/SA0_1") (pintype "bidirectional"))
    )
    (net (code "41") (name "Net-(U5-MODE)") (class "Default")
      (node (ref "MOT_MODE_L/3") (pin "1") (pinfunction "1_1") (pintype "passive"))
      (node (ref "U5") (pin "11") (pinfunction "MODE_11") (pintype "bidirectional"))
    )
    (net (code "42") (name "Net-(U6-MODE)") (class "Default")
      (node (ref "MOT_MODE_R/4") (pin "1") (pinfunction "1_1") (pintype "passive"))
      (node (ref "U6") (pin "11") (pinfunction "MODE_11") (pintype "bidirectional"))
    )
    (net (code "43") (name "RP_IO0{slash}ENC_3_A") (class "Default")
      (node (ref "J3") (pin "4") (pinfunction "4_4") (pintype "bidirectional"))
      (node (ref "TP1") (pin "1") (pinfunction "1_1") (pintype "bidirectional"))
      (node (ref "U1") (pin "1") (pinfunction "GPIO0_1") (pintype "bidirectional"))
    )
    (net (code "44") (name "RP_IO1{slash}ENC_3_B") (class "Default")
      (node (ref "J3") (pin "5") (pinfunction "5_5") (pintype "bidirectional"))
      (node (ref "TP2") (pin "1") (pinfunction "1_1") (pintype "bidirectional"))
      (node (ref "U1") (pin "2") (pinfunction "GPIO1_2") (pintype "bidirectional"))
    )
    (net (code "45") (name "RP_IO2{slash}MOT_3_PH") (class "Default")
      (node (ref "TP3") (pin "1") (pinfunction "1_1") (pintype "bidirectional"))
      (node (ref "U1") (pin "4") (pinfunction "GPIO2_4") (pintype "bidirectional"))
      (node (ref "U5") (pin "8") (pinfunction "BIN1/PH_8") (pintype "bidirectional"))
    )
    (net (code "46") (name "RP_IO3{slash}MOT_3_EN") (class "Default")
      (node (ref "TP4") (pin "1") (pinfunction "1_1") (pintype "bidirectional"))
      (node (ref "U1") (pin "5") (pinfunction "GPIO3_5") (pintype "bidirectional"))
      (node (ref "U5") (pin "7") (pinfunction "BIN2/EN_7") (pintype "bidirectional"))
    )
    (net (code "47") (name "RP_IO4{slash}ENC_L_A") (class "Default")
      (node (ref "J4") (pin "4") (pinfunction "4_4") (pintype "bidirectional"))
      (node (ref "TP5") (pin "1") (pinfunction "1_1") (pintype "bidirectional"))
      (node (ref "U1") (pin "6") (pinfunction "GPIO4_6") (pintype "bidirectional"))
    )
    (net (code "48") (name "RP_IO5{slash}ENC_L_B") (class "Default")
      (node (ref "J4") (pin "5") (pinfunction "5_5") (pintype "bidirectional"))
      (node (ref "TP6") (pin "1") (pinfunction "1_1") (pintype "bidirectional"))
      (node (ref "U1") (pin "7") (pinfunction "GPIO5_7") (pintype "bidirectional"))
    )
    (net (code "49") (name "RP_IO6{slash}MOT_L_PH") (class "Default")
      (node (ref "TP7") (pin "1") (pinfunction "1_1") (pintype "bidirectional"))
      (node (ref "U1") (pin "9") (pinfunction "GPIO6_9") (pintype "bidirectional"))
      (node (ref "U5") (pin "10") (pinfunction "AIN1/PH_10") (pintype "bidirectional"))
    )
    (net (code "50") (name "RP_IO7{slash}MOT_L_EN") (class "Default")
      (node (ref "TP8") (pin "1") (pinfunction "1_1") (pintype "bidirectional"))
      (node (ref "U1") (pin "10") (pinfunction "GPIO7_10") (pintype "bidirectional"))
      (node (ref "U5") (pin "9") (pinfunction "AIN2/EN_9") (pintype "bidirectional"))
    )
    (net (code "51") (name "RP_IO8{slash}ENC_4_A") (class "Default")
      (node (ref "J6") (pin "4") (pinfunction "4_4") (pintype "bidirectional"))
      (node (ref "TP9") (pin "1") (pinfunction "1_1") (pintype "bidirectional"))
      (node (ref "U1") (pin "11") (pinfunction "GPIO8_11") (pintype "bidirectional"))
    )
    (net (code "52") (name "RP_IO9{slash}ENC_4_B") (class "Default")
      (node (ref "J6") (pin "5") (pinfunction "5_5") (pintype "bidirectional"))
      (node (ref "TP10") (pin "1") (pinfunction "1_1") (pintype "bidirectional"))
      (node (ref "U1") (pin "12") (pinfunction "GPIO9_12") (pintype "bidirectional"))
    )
    (net (code "53") (name "RP_IO10{slash}MOT_4_PH") (class "Default")
      (node (ref "TP11") (pin "1") (pinfunction "1_1") (pintype "bidirectional"))
      (node (ref "U1") (pin "14") (pinfunction "GPIO10_14") (pintype "bidirectional"))
      (node (ref "U6") (pin "10") (pinfunction "AIN1/PH_10") (pintype "bidirectional"))
    )
    (net (code "54") (name "RP_IO11{slash}MOT_4_EN") (class "Default")
      (node (ref "TP12") (pin "1") (pinfunction "1_1") (pintype "bidirectional"))
      (node (ref "U1") (pin "15") (pinfunction "GPIO11_15") (pintype "bidirectional"))
      (node (ref "U6") (pin "9") (pinfunction "AIN2/EN_9") (pintype "bidirectional"))
    )
    (net (code "55") (name "RP_IO12{slash}ENC_R_A") (class "Default")
      (node (ref "J5") (pin "4") (pinfunction "4_4") (pintype "bidirectional"))
      (node (ref "TP13") (pin "1") (pinfunction "1_1") (pintype "bidirectional"))
      (node (ref "U1") (pin "16") (pinfunction "GPIO12_16") (pintype "bidirectional"))
    )
    (net (code "56") (name "RP_IO13{slash}ENC_R_B") (class "Default")
      (node (ref "J5") (pin "5") (pinfunction "5_5") (pintype "bidirectional"))
      (node (ref "TP14") (pin "1") (pinfunction "1_1") (pintype "bidirectional"))
      (node (ref "U1") (pin "17") (pinfunction "GPIO13_17") (pintype "bidirectional"))
    )
    (net (code "57") (name "RP_IO14{slash}MOT_R_PH") (class "Default")
      (node (ref "TP15") (pin "1") (pinfunction "1_1") (pintype "bidirectional"))
      (node (ref "U1") (pin "19") (pinfunction "GPIO14_19") (pintype "bidirectional"))
      (node (ref "U6") (pin "8") (pinfunction "BIN1/PH_8") (pintype "bidirectional"))
    )
    (net (code "58") (name "RP_IO15{slash}MOT_R_EN") (class "Default")
      (node (ref "TP16") (pin "1") (pinfunction "1_1") (pintype "bidirectional"))
      (node (ref "U1") (pin "20") (pinfunction "GPIO15_20") (pintype "bidirectional"))
      (node (ref "U6") (pin "7") (pinfunction "BIN2/EN_7") (pintype "bidirectional"))
    )
    (net (code "59") (name "RP_IO16{slash}S1_OUT") (class "Default")
      (node (ref "J7") (pin "3") (pinfunction "3_3") (pintype "passive"))
      (node (ref "U1") (pin "21") (pinfunction "GPIO16_21") (pintype "bidirectional"))
    )
    (net (code "60") (name "RP_IO17{slash}S2_OUT") (class "Default")
      (node (ref "J8") (pin "1") (pinfunction "1_1") (pintype "passive"))
      (node (ref "U1") (pin "22") (pinfunction "GPIO17_22") (pintype "bidirectional"))
    )
    (net (code "61") (name "RP_IO18{slash}SDA") (class "Default")
      (node (ref "J9") (pin "3") (pinfunction "3_3") (pintype "passive"))
      (node (ref "R1") (pin "1") (pinfunction "1_1") (pintype "passive"))
      (node (ref "TP17") (pin "1") (pinfunction "1_1") (pintype "bidirectional"))
      (node (ref "U1") (pin "24") (pinfunction "GPIO18_24") (pintype "bidirectional"))
      (node (ref "U4") (pin "14") (pinfunction "SDA_14") (pintype "bidirectional"))
    )
    (net (code "62") (name "RP_IO19{slash}SCL") (class "Default")
      (node (ref "J9") (pin "4") (pinfunction "4_4") (pintype "passive"))
      (node (ref "R2") (pin "2") (pinfunction "2_2") (pintype "passive"))
      (node (ref "TP18") (pin "1") (pinfunction "1_1") (pintype "bidirectional"))
      (node (ref "U1") (pin "25") (pinfunction "GPIO19_25") (pintype "bidirectional"))
      (node (ref "U4") (pin "13") (pinfunction "SCL_13") (pintype "bidirectional"))
    )
    (net (code "63") (name "RP_IO20{slash}RANGE_TRIG") (class "Default")
      (node (ref "J12") (pin "3") (pinfunction "3_3") (pintype "passive"))
      (node (ref "TP19") (pin "1") (pinfunction "1_1") (pintype "bidirectional"))
      (node (ref "U1") (pin "26") (pinfunction "GPIO20_26") (pintype "bidirectional"))
    )
    (net (code "64") (name "RP_IO21{slash}RANGE_ECHO") (class "Default")
      (node (ref "J12") (pin "4") (pinfunction "4_4") (pintype "passive"))
      (node (ref "TP20") (pin "1") (pinfunction "1_1") (pintype "bidirectional"))
      (node (ref "U1") (pin "27") (pinfunction "GPIO21_27") (pintype "bidirectional"))
    )
    (net (code "65") (name "RP_IO22{slash}USER_BTN") (class "Default")
      (node (ref "J13") (pin "3") (pinfunction "3_3") (pintype "passive"))
      (node (ref "TP21") (pin "1") (pinfunction "1_1") (pintype "bidirectional"))
      (node (ref "U1") (pin "29") (pinfunction "GPIO22_29") (pintype "bidirectional"))
      (node (ref "USER_BTN") (pin "2") (pinfunction "2_2") (pintype "passive"))
    )
    (net (code "66") (name "RP_IO26{slash}LINE_L") (class "Default")
      (node (ref "J14") (pin "3") (pinfunction "3_3") (pintype "passive"))
      (node (ref "TP22") (pin "1") (pinfunction "1_1") (pintype "bidirectional"))
      (node (ref "U1") (pin "31") (pinfunction "GPIO26/ADC0_31") (pintype "bidirectional"))
    )
    (net (code "67") (name "RP_IO27{slash}LINE_R") (class "Default")
      (node (ref "J14") (pin "4") (pinfunction "4_4") (pintype "passive"))
      (node (ref "TP23") (pin "1") (pinfunction "1_1") (pintype "bidirectional"))
      (node (ref "U1") (pin "32") (pinfunction "GPIO27/ADC1_32") (pintype "bidirectional"))
    )
    (net (code "68") (name "RP_IO28{slash}VIN_MEAS") (class "Default")
      (node (ref "J13") (pin "4") (pinfunction "4_4") (pintype "passive"))
      (node (ref "TP24") (pin "1") (pinfunction "1_1") (pintype "bidirectional"))
      (node (ref "U1") (pin "34") (pinfunction "GPIO28/ADC2_34") (pintype "bidirectional"))
      (node (ref "VIN_MEAS") (pin "1") (pinfunction "1_1") (pintype "passive"))
    )
    (net (code "69") (name "VIN") (class "Default")
      (node (ref "C3") (pin "+") (pinfunction "+_+") (pintype "passive"))
      (node (ref "C5") (pin "+") (pinfunction "+_+") (pintype "passive"))
      (node (ref "C7") (pin "1") (pinfunction "1_1") (pintype "passive"))
      (node (ref "C8") (pin "1") (pinfunction "1_1") (pintype "passive"))
      (node (ref "C9") (pin "1") (pinfunction "1_1") (pintype "passive"))
      (node (ref "F1") (pin "2") (pinfunction "2_2") (pintype "bidirectional"))
      (node (ref "R16") (pin "2") (pinfunction "2_2") (pintype "passive"))
      (node (ref "U2") (pin "P$1") (pinfunction "VIN_P$1") (pintype "power_in"))
      (node (ref "U5") (pin "1") (pinfunction "VM_1") (pintype "bidirectional"))
      (node (ref "U6") (pin "1") (pinfunction "VM_1") (pintype "bidirectional"))
    )
    (net (code "70") (name "V_BATT") (class "Default")
      (node (ref "J1") (pin "PWR") (pinfunction "PWR_PWR") (pintype "bidirectional"))
      (node (ref "Q1") (pin "1") (pinfunction "E_1") (pintype "passive"))
      (node (ref "Q3") (pin "3") (pinfunction "D_3") (pintype "bidirectional"))
      (node (ref "TP34") (pin "1") (pinfunction "1_1") (pintype "bidirectional"))
    )
    (net (code "71") (name "V_POW") (class "Default")
      (node (ref "Q1") (pin "4") (pinfunction "E_4") (pintype "passive"))
      (node (ref "Q2") (pin "4") (pinfunction "E_4") (pintype "passive"))
      (node (ref "Q3") (pin "2") (pinfunction "S_2") (pintype "bidirectional"))
      (node (ref "Q4") (pin "2") (pinfunction "S_2") (pintype "bidirectional"))
      (node (ref "Q6") (pin "2") (pinfunction "S_2") (pintype "bidirectional"))
      (node (ref "R12") (pin "2") (pinfunction "2_2") (pintype "passive"))
    )
    (net (code "72") (name "V_SYS") (class "Default")
      (node (ref "Q5") (pin "2") (pinfunction "S_2") (pintype "bidirectional"))
      (node (ref "Q7") (pin "4") (pinfunction "E_4") (pintype "passive"))
      (node (ref "U1") (pin "39") (pinfunction "VSYS_39") (pintype "bidirectional"))
    )
    (net (code "73") (name "V_USB") (class "Default")
      (node (ref "Q2") (pin "1") (pinfunction "E_1") (pintype "passive"))
      (node (ref "Q4") (pin "3") (pinfunction "D_3") (pintype "bidirectional"))
      (node (ref "R18") (pin "2") (pinfunction "2_2") (pintype "passive"))
      (node (ref "R19") (pin "2") (pinfunction "2_2") (pintype "passive"))
    )
    (net (code "74") (name "unconnected-(J1-PadGNDBREAK)") (class "Default")
      (node (ref "J1") (pin "GNDBREAK") (pinfunction "GNDBREAK_GNDBREAK") (pintype "bidirectional"))
    )
    (net (code "75") (name "unconnected-(S1-O-Pad1)") (class "Default")
      (node (ref "S1") (pin "1") (pinfunction "O_1") (pintype "passive"))
    )
    (net (code "76") (name "unconnected-(U1-3V3_EN-Pad37)") (class "Default")
      (node (ref "U1") (pin "37") (pinfunction "3V3_EN_37") (pintype "bidirectional"))
    )
    (net (code "77") (name "unconnected-(U1-ADC_VREF-Pad35)") (class "Default")
      (node (ref "U1") (pin "35") (pinfunction "ADC_VREF_35") (pintype "bidirectional"))
    )
    (net (code "78") (name "unconnected-(U1-SWCLK-Pad47)") (class "Default")
      (node (ref "U1") (pin "47") (pinfunction "SWCLK_47") (pintype "bidirectional"))
    )
    (net (code "79") (name "unconnected-(U1-SWDIO-Pad49)") (class "Default")
      (node (ref "U1") (pin "49") (pinfunction "SWDIO_49") (pintype "bidirectional"))
    )
    (net (code "80") (name "unconnected-(U1-TP_USB_D+-Pad43)") (class "Default")
      (node (ref "U1") (pin "43") (pinfunction "TP_USB_D+_43") (pintype "bidirectional"))
    )
    (net (code "81") (name "unconnected-(U1-TP_USB_D--Pad42)") (class "Default")
      (node (ref "U1") (pin "42") (pinfunction "TP_USB_D-_42") (pintype "bidirectional"))
    )
    (net (code "82") (name "unconnected-(U1-TP_WL_GPIO0-Pad45)") (class "Default")
      (node (ref "U1") (pin "45") (pinfunction "TP_WL_GPIO0_45") (pintype "bidirectional"))
    )
    (net (code "83") (name "unconnected-(U1-TP_WL_GPIO1-Pad44)") (class "Default")
      (node (ref "U1") (pin "44") (pinfunction "TP_WL_GPIO1_44") (pintype "bidirectional"))
    )
    (net (code "84") (name "unconnected-(U4-OCSX-Pad10)") (class "Default")
      (node (ref "U4") (pin "10") (pinfunction "OCSX_10") (pintype "bidirectional"))
    )
    (net (code "85") (name "unconnected-(U4-SDOX-Pad11)") (class "Default")
      (node (ref "U4") (pin "11") (pinfunction "SDOX_11") (pintype "bidirectional"))
    )
    (net (code "86") (name "unconnected-(U4-~{CS}-Pad12)") (class "Default")
      (node (ref "U4") (pin "12") (pinfunction "~{CS}_12") (pintype "bidirectional"))
    )
  )
)
